# hw-art_v1.net
KiCad netlist of a schematic drawn in EAGLE
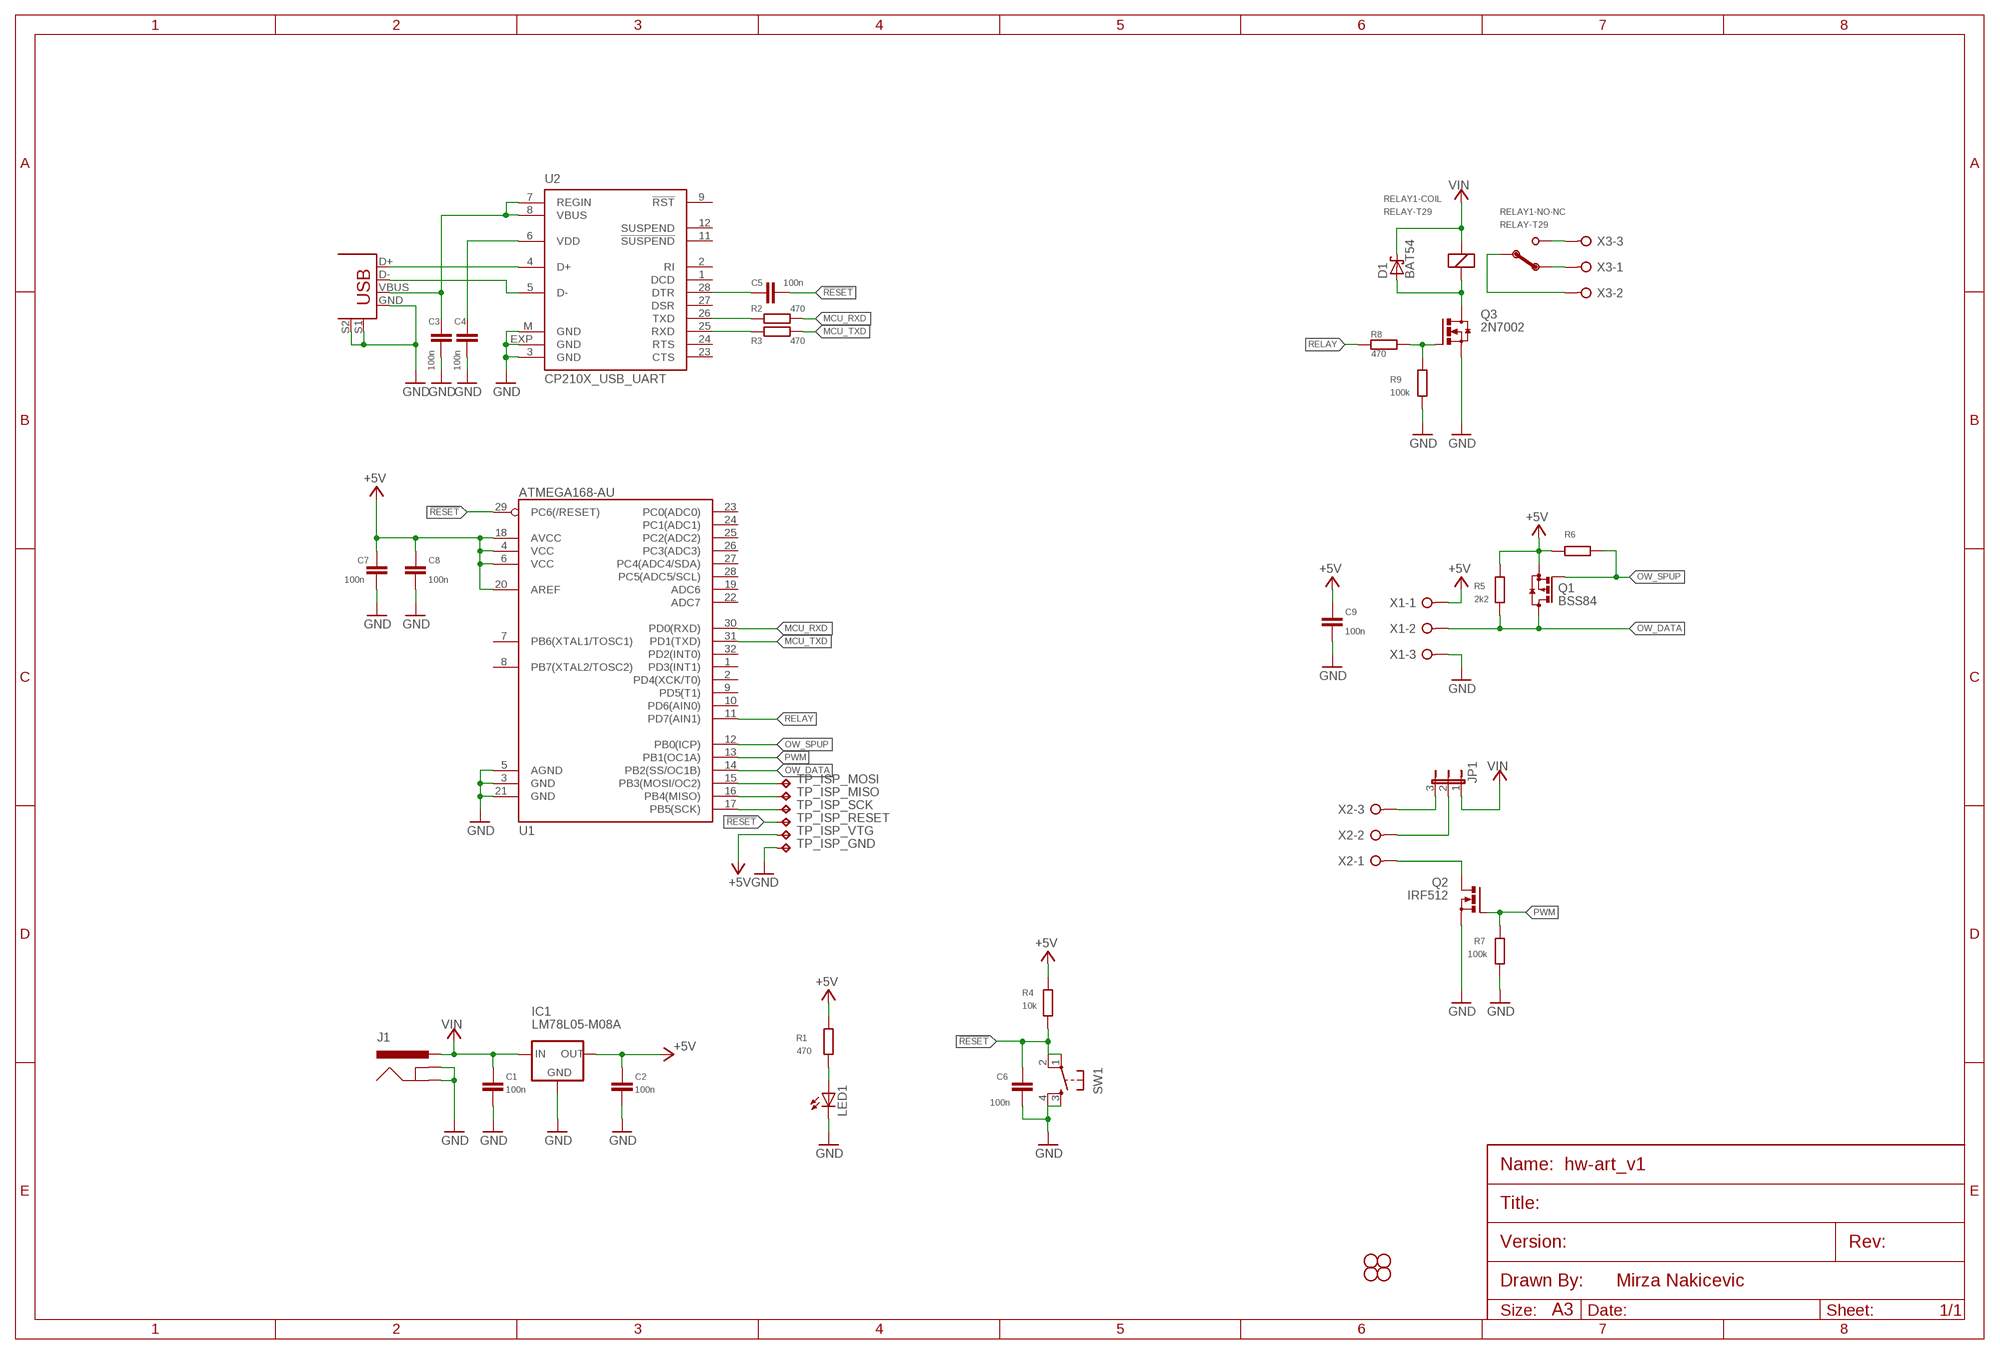
[diagram p0: schematic, sheet 1]

(export (version "E")
  (design (tool "Eeschema 10.0.6"))
  (components
    (comp (ref "C1")
      (value "100n")
      (footprint "eagle-import:C0603")
      (libsource (lib "eagle-import") (part "C-0603"))
    )
    (comp (ref "C2")
      (value "100n")
      (footprint "eagle-import:C0603")
      (libsource (lib "eagle-import") (part "C-0603"))
    )
    (comp (ref "C3")
      (value "100n")
      (footprint "eagle-import:C0603")
      (libsource (lib "eagle-import") (part "C-0603"))
    )
    (comp (ref "C4")
      (value "100n")
      (footprint "eagle-import:C0603")
      (libsource (lib "eagle-import") (part "C-0603"))
    )
    (comp (ref "C5")
      (value "100n")
      (footprint "eagle-import:C0603")
      (libsource (lib "eagle-import") (part "C-0603"))
    )
    (comp (ref "C6")
      (value "100n")
      (footprint "eagle-import:C0603")
      (libsource (lib "eagle-import") (part "C-0603"))
    )
    (comp (ref "C7")
      (value "100n")
      (footprint "eagle-import:C0603")
      (libsource (lib "eagle-import") (part "C-0603"))
    )
    (comp (ref "C8")
      (value "100n")
      (footprint "eagle-import:C0603")
      (libsource (lib "eagle-import") (part "C-0603"))
    )
    (comp (ref "C9")
      (value "100n")
      (footprint "eagle-import:C0603")
      (libsource (lib "eagle-import") (part "C-0603"))
    )
    (comp (ref "D1")
      (value "BAT54")
      (footprint "eagle-import:SOT23")
      (libsource (lib "eagle-import") (part "BAT54"))
    )
    (comp (ref "IC1")
      (value "LM78L05-M08A")
      (footprint "eagle-import:SO-08")
      (libsource (lib "eagle-import") (part "LM78L05-M08A"))
    )
    (comp (ref "J1")
      (value "DCJACK-05537")
      (footprint "eagle-import:4UCON-05537")
      (libsource (lib "eagle-import") (part "DCJACK-05537"))
    )
    (comp (ref "J2")
      (value "USB+SHIELD")
      (footprint "eagle-import:USB-B-PTH")
      (libsource (lib "eagle-import") (part "USB+SHIELD"))
    )
    (comp (ref "JP1")
      (value "JP2E")
      (footprint "eagle-import:JP2")
      (libsource (lib "eagle-import") (part "JP2E"))
    )
    (comp (ref "LED1")
      (value "LEDCHIP-LED0805")
      (footprint "eagle-import:CHIP-LED0805")
      (libsource (lib "eagle-import") (part "LEDCHIP-LED0805"))
    )
    (comp (ref "Q1")
      (value "BSS84")
      (footprint "eagle-import:SOT23")
      (libsource (lib "eagle-import") (part "BSS84"))
    )
    (comp (ref "Q2")
      (value "IRF512")
      (footprint "eagle-import:TO220BV")
      (libsource (lib "eagle-import") (part "IRF512"))
    )
    (comp (ref "Q3")
      (value "2N7002")
      (footprint "eagle-import:SOT-23")
      (libsource (lib "eagle-import") (part "2N7002"))
    )
    (comp (ref "R1")
      (value "470")
      (footprint "eagle-import:R0603")
      (libsource (lib "eagle-import") (part "R-0603"))
    )
    (comp (ref "R2")
      (value "470")
      (footprint "eagle-import:R0603")
      (libsource (lib "eagle-import") (part "R-0603"))
    )
    (comp (ref "R3")
      (value "470")
      (footprint "eagle-import:R0603")
      (libsource (lib "eagle-import") (part "R-0603"))
    )
    (comp (ref "R4")
      (value "10k")
      (footprint "eagle-import:R0603")
      (libsource (lib "eagle-import") (part "R-0603"))
    )
    (comp (ref "R5")
      (value "2k2")
      (footprint "eagle-import:R0603")
      (libsource (lib "eagle-import") (part "R-0603"))
    )
    (comp (ref "R6")
      (value "R-0603")
      (footprint "eagle-import:R0603")
      (libsource (lib "eagle-import") (part "R-0603"))
    )
    (comp (ref "R7")
      (value "100k")
      (footprint "eagle-import:R0603")
      (libsource (lib "eagle-import") (part "R-0603"))
    )
    (comp (ref "R8")
      (value "470")
      (footprint "eagle-import:R0603")
      (libsource (lib "eagle-import") (part "R-0603"))
    )
    (comp (ref "R9")
      (value "100k")
      (footprint "eagle-import:R0603")
      (libsource (lib "eagle-import") (part "R-0603"))
    )
    (comp (ref "RELAY1")
      (value "RELAY-T29")
      (footprint "eagle-import:FINDER_T29")
      (libsource (lib "eagle-import") (part "RELAY-T29"))
    )
    (comp (ref "SW1")
      (value "TAC_SWITCHPTH")
      (footprint "eagle-import:TACTILE-PTH")
      (libsource (lib "eagle-import") (part "TAC_SWITCHPTH"))
    )
    (comp (ref "TP_ISP_GND")
      (value "TPTP08R")
      (footprint "eagle-import:TP08R")
      (libsource (lib "eagle-import") (part "TPTP08R"))
    )
    (comp (ref "TP_ISP_MISO")
      (value "TPTP08R")
      (footprint "eagle-import:TP08R")
      (libsource (lib "eagle-import") (part "TPTP08R"))
    )
    (comp (ref "TP_ISP_MOSI")
      (value "TPTP08R")
      (footprint "eagle-import:TP08R")
      (libsource (lib "eagle-import") (part "TPTP08R"))
    )
    (comp (ref "TP_ISP_RESET")
      (value "TPTP08R")
      (footprint "eagle-import:TP08R")
      (libsource (lib "eagle-import") (part "TPTP08R"))
    )
    (comp (ref "TP_ISP_SCK")
      (value "TPTP08R")
      (footprint "eagle-import:TP08R")
      (libsource (lib "eagle-import") (part "TPTP08R"))
    )
    (comp (ref "TP_ISP_VTG")
      (value "TPTP08R")
      (footprint "eagle-import:TP08R")
      (libsource (lib "eagle-import") (part "TPTP08R"))
    )
    (comp (ref "U$1")
      (value "STAND-OFF")
      (footprint "eagle-import:STAND-OFF")
      (libsource (lib "eagle-import") (part "STAND-OFF"))
    )
    (comp (ref "U$2")
      (value "STAND-OFF")
      (footprint "eagle-import:STAND-OFF")
      (libsource (lib "eagle-import") (part "STAND-OFF"))
    )
    (comp (ref "U$3")
      (value "STAND-OFF")
      (footprint "eagle-import:STAND-OFF")
      (libsource (lib "eagle-import") (part "STAND-OFF"))
    )
    (comp (ref "U$4")
      (value "STAND-OFF")
      (footprint "eagle-import:STAND-OFF")
      (libsource (lib "eagle-import") (part "STAND-OFF"))
    )
    (comp (ref "U1")
      (value "ATMEGA168-AU")
      (footprint "eagle-import:TQFP32-08")
      (libsource (lib "eagle-import") (part "ATMEGA168-AU"))
    )
    (comp (ref "U2")
      (value "CP210X_USB_UART")
      (footprint "eagle-import:MLP28")
      (libsource (lib "eagle-import") (part "CP210X_USB_UART"))
    )
    (comp (ref "X1")
      (value "W237-03P")
      (footprint "eagle-import:W237-133")
      (libsource (lib "eagle-import") (part "W237-03P"))
    )
    (comp (ref "X2")
      (value "W237-03P")
      (footprint "eagle-import:W237-133")
      (libsource (lib "eagle-import") (part "W237-03P"))
    )
    (comp (ref "X3")
      (value "W237-03P")
      (footprint "eagle-import:W237-133")
      (libsource (lib "eagle-import") (part "W237-03P"))
    )
  )
  (nets
    (net (code "1") (name "+5V") (class "Default")
      (node (ref "C2") (pin "1") (pinfunction "1_1") (pintype "passive"))
      (node (ref "C7") (pin "1") (pinfunction "1_1") (pintype "passive"))
      (node (ref "C8") (pin "1") (pinfunction "1_1") (pintype "passive"))
      (node (ref "C9") (pin "1") (pinfunction "1_1") (pintype "passive"))
      (node (ref "IC1") (pin "1") (pinfunction "OUT_1") (pintype "output"))
      (node (ref "Q1") (pin "2") (pinfunction "S_2") (pintype "passive"))
      (node (ref "R1") (pin "2") (pinfunction "2_2") (pintype "passive"))
      (node (ref "R4") (pin "2") (pinfunction "2_2") (pintype "passive"))
      (node (ref "R5") (pin "2") (pinfunction "2_2") (pintype "passive"))
      (node (ref "R6") (pin "1") (pinfunction "1_1") (pintype "passive"))
      (node (ref "TP_ISP_VTG") (pin "TP") (pinfunction "TP_TP") (pintype "input"))
      (node (ref "U1") (pin "18") (pinfunction "AVCC_18") (pintype "bidirectional"))
      (node (ref "U1") (pin "20") (pinfunction "AREF_20") (pintype "bidirectional"))
      (node (ref "U1") (pin "4") (pinfunction "VCC_4") (pintype "bidirectional"))
      (node (ref "U1") (pin "6") (pinfunction "VCC_6") (pintype "bidirectional"))
      (node (ref "X1") (pin "1") (pinfunction "KL_1") (pintype "passive"))
    )
    (net (code "2") (name "/~{RESET}") (class "Default")
      (node (ref "C5") (pin "2") (pinfunction "2_2") (pintype "passive"))
      (node (ref "C6") (pin "2") (pinfunction "2_2") (pintype "passive"))
      (node (ref "R4") (pin "1") (pinfunction "1_1") (pintype "passive"))
      (node (ref "SW1") (pin "1") (pinfunction "1_1") (pintype "passive"))
      (node (ref "SW1") (pin "2") (pinfunction "2_2") (pintype "passive"))
      (node (ref "TP_ISP_RESET") (pin "TP") (pinfunction "TP_TP") (pintype "input"))
      (node (ref "U1") (pin "29") (pinfunction "PC6(/RESET)_29") (pintype "bidirectional"))
    )
    (net (code "3") (name "GND") (class "Default")
      (node (ref "C1") (pin "2") (pinfunction "2_2") (pintype "passive"))
      (node (ref "C2") (pin "2") (pinfunction "2_2") (pintype "passive"))
      (node (ref "C3") (pin "2") (pinfunction "2_2") (pintype "passive"))
      (node (ref "C4") (pin "2") (pinfunction "2_2") (pintype "passive"))
      (node (ref "C6") (pin "1") (pinfunction "1_1") (pintype "passive"))
      (node (ref "C7") (pin "2") (pinfunction "2_2") (pintype "passive"))
      (node (ref "C8") (pin "2") (pinfunction "2_2") (pintype "passive"))
      (node (ref "C9") (pin "2") (pinfunction "2_2") (pintype "passive"))
      (node (ref "IC1") (pin "2") (pinfunction "GND_2") (pintype "input"))
      (node (ref "IC1") (pin "3") (pinfunction "GND_3") (pintype "input"))
      (node (ref "IC1") (pin "6") (pinfunction "GND_6") (pintype "input"))
      (node (ref "IC1") (pin "7") (pinfunction "GND_7") (pintype "input"))
      (node (ref "J1") (pin "2") (pinfunction "GND_2") (pintype "bidirectional"))
      (node (ref "J1") (pin "3") (pinfunction "GNDBREAK_3") (pintype "bidirectional"))
      (node (ref "J2") (pin "GND") (pinfunction "GND_GND") (pintype "bidirectional"))
      (node (ref "J2") (pin "S1") (pinfunction "P$1_S1") (pintype "bidirectional"))
      (node (ref "J2") (pin "S2") (pinfunction "P$2_S2") (pintype "bidirectional"))
      (node (ref "LED1") (pin "C") (pinfunction "C_C") (pintype "passive"))
      (node (ref "Q2") (pin "S") (pinfunction "S_S") (pintype "passive"))
      (node (ref "Q3") (pin "2") (pinfunction "S_2") (pintype "passive"))
      (node (ref "R7") (pin "2") (pinfunction "2_2") (pintype "passive"))
      (node (ref "R9") (pin "1") (pinfunction "1_1") (pintype "passive"))
      (node (ref "SW1") (pin "3") (pinfunction "3_3") (pintype "passive"))
      (node (ref "SW1") (pin "4") (pinfunction "4_4") (pintype "passive"))
      (node (ref "TP_ISP_GND") (pin "TP") (pinfunction "TP_TP") (pintype "input"))
      (node (ref "U1") (pin "21") (pinfunction "GND_21") (pintype "bidirectional"))
      (node (ref "U1") (pin "3") (pinfunction "GND_3") (pintype "bidirectional"))
      (node (ref "U1") (pin "5") (pinfunction "AGND_5") (pintype "bidirectional"))
      (node (ref "U2") (pin "3") (pinfunction "GND_3") (pintype "power_in"))
      (node (ref "U2") (pin "EXP") (pinfunction "GND_EXP") (pintype "power_in"))
      (node (ref "U2") (pin "M") (pinfunction "GND_M") (pintype "power_in"))
      (node (ref "X1") (pin "3") (pinfunction "KL_3") (pintype "passive"))
    )
    (net (code "4") (name "MCU_RXD") (class "Default")
      (node (ref "R2") (pin "2") (pinfunction "2_2") (pintype "passive"))
      (node (ref "U1") (pin "30") (pinfunction "PD0(RXD)_30") (pintype "bidirectional"))
    )
    (net (code "5") (name "MCU_TXD") (class "Default")
      (node (ref "R3") (pin "2") (pinfunction "2_2") (pintype "passive"))
      (node (ref "U1") (pin "31") (pinfunction "PD1(TXD)_31") (pintype "bidirectional"))
    )
    (net (code "6") (name "Net-(D1-A)") (class "Default")
      (node (ref "D1") (pin "1") (pinfunction "A_1") (pintype "passive"))
      (node (ref "Q3") (pin "3") (pinfunction "D_3") (pintype "passive"))
      (node (ref "RELAY1") (pin "-") (pinfunction "P$2_-") (pintype "bidirectional"))
    )
    (net (code "7") (name "Net-(LED1-PadA)") (class "Default")
      (node (ref "LED1") (pin "A") (pinfunction "A_A") (pintype "passive"))
      (node (ref "R1") (pin "1") (pinfunction "1_1") (pintype "passive"))
    )
    (net (code "8") (name "Net-(Q3-G)") (class "Default")
      (node (ref "Q3") (pin "1") (pinfunction "G_1") (pintype "passive"))
      (node (ref "R8") (pin "1") (pinfunction "1_1") (pintype "passive"))
      (node (ref "R9") (pin "2") (pinfunction "2_2") (pintype "passive"))
    )
    (net (code "9") (name "Net-(U1-PB3(MOSI{slash}OC2))") (class "Default")
      (node (ref "TP_ISP_MOSI") (pin "TP") (pinfunction "TP_TP") (pintype "input"))
      (node (ref "U1") (pin "15") (pinfunction "PB3(MOSI/OC2)_15") (pintype "bidirectional"))
    )
    (net (code "10") (name "Net-(U1-PB4(MISO))") (class "Default")
      (node (ref "TP_ISP_MISO") (pin "TP") (pinfunction "TP_TP") (pintype "input"))
      (node (ref "U1") (pin "16") (pinfunction "PB4(MISO)_16") (pintype "bidirectional"))
    )
    (net (code "11") (name "Net-(U1-PB5(SCK))") (class "Default")
      (node (ref "TP_ISP_SCK") (pin "TP") (pinfunction "TP_TP") (pintype "input"))
      (node (ref "U1") (pin "17") (pinfunction "PB5(SCK)_17") (pintype "bidirectional"))
    )
    (net (code "12") (name "Net-(U2-D+)") (class "Default")
      (node (ref "J2") (pin "D+") (pinfunction "D+_D+") (pintype "bidirectional"))
      (node (ref "U2") (pin "4") (pinfunction "D+_4") (pintype "bidirectional"))
    )
    (net (code "13") (name "Net-(U2-D-)") (class "Default")
      (node (ref "J2") (pin "D-") (pinfunction "D-_D-") (pintype "bidirectional"))
      (node (ref "U2") (pin "5") (pinfunction "D-_5") (pintype "bidirectional"))
    )
    (net (code "14") (name "Net-(U2-DTR)") (class "Default")
      (node (ref "C5") (pin "1") (pinfunction "1_1") (pintype "passive"))
      (node (ref "U2") (pin "28") (pinfunction "DTR_28") (pintype "output"))
    )
    (net (code "15") (name "Net-(U2-REGIN)") (class "Default")
      (node (ref "C3") (pin "1") (pinfunction "1_1") (pintype "passive"))
      (node (ref "J2") (pin "VBUS") (pinfunction "VBUS_VBUS") (pintype "bidirectional"))
      (node (ref "U2") (pin "7") (pinfunction "REGIN_7") (pintype "passive"))
      (node (ref "U2") (pin "8") (pinfunction "VBUS_8") (pintype "input"))
    )
    (net (code "16") (name "Net-(U2-RXD)") (class "Default")
      (node (ref "R3") (pin "1") (pinfunction "1_1") (pintype "passive"))
      (node (ref "U2") (pin "25") (pinfunction "RXD_25") (pintype "input"))
    )
    (net (code "17") (name "Net-(U2-TXD)") (class "Default")
      (node (ref "R2") (pin "1") (pinfunction "1_1") (pintype "passive"))
      (node (ref "U2") (pin "26") (pinfunction "TXD_26") (pintype "output"))
    )
    (net (code "18") (name "Net-(U2-VDD)") (class "Default")
      (node (ref "C4") (pin "1") (pinfunction "1_1") (pintype "passive"))
      (node (ref "U2") (pin "6") (pinfunction "VDD_6") (pintype "power_in"))
    )
    (net (code "19") (name "Net-(X2A-KL)") (class "Default")
      (node (ref "Q2") (pin "D") (pinfunction "D_D") (pintype "passive"))
      (node (ref "X2") (pin "1") (pinfunction "KL_1") (pintype "passive"))
    )
    (net (code "20") (name "Net-(X2B-KL)") (class "Default")
      (node (ref "JP1") (pin "2") (pinfunction "2_2") (pintype "passive"))
      (node (ref "X2") (pin "2") (pinfunction "KL_2") (pintype "passive"))
    )
    (net (code "21") (name "Net-(X2C-KL)") (class "Default")
      (node (ref "JP1") (pin "3") (pinfunction "3_3") (pintype "passive"))
      (node (ref "X2") (pin "3") (pinfunction "KL_3") (pintype "passive"))
    )
    (net (code "22") (name "Net-(X3A-KL)") (class "Default")
      (node (ref "RELAY1") (pin "NC") (pinfunction "NC_NC") (pintype "bidirectional"))
      (node (ref "X3") (pin "1") (pinfunction "KL_1") (pintype "passive"))
    )
    (net (code "23") (name "Net-(X3B-KL)") (class "Default")
      (node (ref "RELAY1") (pin "COM") (pinfunction "COM_COM") (pintype "bidirectional"))
      (node (ref "X3") (pin "2") (pinfunction "KL_2") (pintype "passive"))
    )
    (net (code "24") (name "Net-(X3C-KL)") (class "Default")
      (node (ref "RELAY1") (pin "NO") (pinfunction "NO_NO") (pintype "bidirectional"))
      (node (ref "X3") (pin "3") (pinfunction "KL_3") (pintype "passive"))
    )
    (net (code "25") (name "OW_DATA") (class "Default")
      (node (ref "Q1") (pin "3") (pinfunction "D_3") (pintype "passive"))
      (node (ref "R5") (pin "1") (pinfunction "1_1") (pintype "passive"))
      (node (ref "U1") (pin "14") (pinfunction "PB2(SS/OC1B)_14") (pintype "bidirectional"))
      (node (ref "X1") (pin "2") (pinfunction "KL_2") (pintype "passive"))
    )
    (net (code "26") (name "OW_SPUP") (class "Default")
      (node (ref "Q1") (pin "1") (pinfunction "G_1") (pintype "passive"))
      (node (ref "R6") (pin "2") (pinfunction "2_2") (pintype "passive"))
      (node (ref "U1") (pin "12") (pinfunction "PB0(ICP)_12") (pintype "bidirectional"))
    )
    (net (code "27") (name "PWM") (class "Default")
      (node (ref "Q2") (pin "G") (pinfunction "G_G") (pintype "passive"))
      (node (ref "R7") (pin "1") (pinfunction "1_1") (pintype "passive"))
      (node (ref "U1") (pin "13") (pinfunction "PB1(OC1A)_13") (pintype "bidirectional"))
    )
    (net (code "28") (name "RELAY") (class "Default")
      (node (ref "R8") (pin "2") (pinfunction "2_2") (pintype "passive"))
      (node (ref "U1") (pin "11") (pinfunction "PD7(AIN1)_11") (pintype "bidirectional"))
    )
    (net (code "29") (name "VIN") (class "Default")
      (node (ref "C1") (pin "1") (pinfunction "1_1") (pintype "passive"))
      (node (ref "D1") (pin "3") (pinfunction "C_3") (pintype "passive"))
      (node (ref "IC1") (pin "8") (pinfunction "IN_8") (pintype "input"))
      (node (ref "J1") (pin "1") (pinfunction "PWR_1") (pintype "bidirectional"))
      (node (ref "JP1") (pin "1") (pinfunction "1_1") (pintype "passive"))
      (node (ref "RELAY1") (pin "+") (pinfunction "P$1_+") (pintype "bidirectional"))
    )
    (net (code "30") (name "unconnected-(U1-ADC6-Pad19)") (class "Default")
      (node (ref "U1") (pin "19") (pinfunction "ADC6_19") (pintype "bidirectional"))
    )
    (net (code "31") (name "unconnected-(U1-ADC7-Pad22)") (class "Default")
      (node (ref "U1") (pin "22") (pinfunction "ADC7_22") (pintype "bidirectional"))
    )
    (net (code "32") (name "unconnected-(U1-PB6(XTAL1{slash}TOSC1)-Pad7)") (class "Default")
      (node (ref "U1") (pin "7") (pinfunction "PB6(XTAL1/TOSC1)_7") (pintype "bidirectional"))
    )
    (net (code "33") (name "unconnected-(U1-PB7(XTAL2{slash}TOSC2)-Pad8)") (class "Default")
      (node (ref "U1") (pin "8") (pinfunction "PB7(XTAL2/TOSC2)_8") (pintype "bidirectional"))
    )
    (net (code "34") (name "unconnected-(U1-PC0(ADC0)-Pad23)") (class "Default")
      (node (ref "U1") (pin "23") (pinfunction "PC0(ADC0)_23") (pintype "bidirectional"))
    )
    (net (code "35") (name "unconnected-(U1-PC1(ADC1)-Pad24)") (class "Default")
      (node (ref "U1") (pin "24") (pinfunction "PC1(ADC1)_24") (pintype "bidirectional"))
    )
    (net (code "36") (name "unconnected-(U1-PC2(ADC2)-Pad25)") (class "Default")
      (node (ref "U1") (pin "25") (pinfunction "PC2(ADC2)_25") (pintype "bidirectional"))
    )
    (net (code "37") (name "unconnected-(U1-PC3(ADC3)-Pad26)") (class "Default")
      (node (ref "U1") (pin "26") (pinfunction "PC3(ADC3)_26") (pintype "bidirectional"))
    )
    (net (code "38") (name "unconnected-(U1-PC4(ADC4{slash}SDA)-Pad27)") (class "Default")
      (node (ref "U1") (pin "27") (pinfunction "PC4(ADC4/SDA)_27") (pintype "bidirectional"))
    )
    (net (code "39") (name "unconnected-(U1-PC5(ADC5{slash}SCL)-Pad28)") (class "Default")
      (node (ref "U1") (pin "28") (pinfunction "PC5(ADC5/SCL)_28") (pintype "bidirectional"))
    )
    (net (code "40") (name "unconnected-(U1-PD2(INT0)-Pad32)") (class "Default")
      (node (ref "U1") (pin "32") (pinfunction "PD2(INT0)_32") (pintype "bidirectional"))
    )
    (net (code "41") (name "unconnected-(U1-PD3(INT1)-Pad1)") (class "Default")
      (node (ref "U1") (pin "1") (pinfunction "PD3(INT1)_1") (pintype "bidirectional"))
    )
    (net (code "42") (name "unconnected-(U1-PD4(XCK{slash}T0)-Pad2)") (class "Default")
      (node (ref "U1") (pin "2") (pinfunction "PD4(XCK/T0)_2") (pintype "bidirectional"))
    )
    (net (code "43") (name "unconnected-(U1-PD5(T1)-Pad9)") (class "Default")
      (node (ref "U1") (pin "9") (pinfunction "PD5(T1)_9") (pintype "bidirectional"))
    )
    (net (code "44") (name "unconnected-(U1-PD6(AIN0)-Pad10)") (class "Default")
      (node (ref "U1") (pin "10") (pinfunction "PD6(AIN0)_10") (pintype "bidirectional"))
    )
    (net (code "45") (name "unconnected-(U2-CTS-Pad23)") (class "Default")
      (node (ref "U2") (pin "23") (pinfunction "CTS_23") (pintype "input"))
    )
    (net (code "46") (name "unconnected-(U2-DCD-Pad1)") (class "Default")
      (node (ref "U2") (pin "1") (pinfunction "DCD_1") (pintype "input"))
    )
    (net (code "47") (name "unconnected-(U2-DSR-Pad27)") (class "Default")
      (node (ref "U2") (pin "27") (pinfunction "DSR_27") (pintype "input"))
    )
    (net (code "48") (name "unconnected-(U2-RI-Pad2)") (class "Default")
      (node (ref "U2") (pin "2") (pinfunction "RI_2") (pintype "input"))
    )
    (net (code "49") (name "unconnected-(U2-RTS-Pad24)") (class "Default")
      (node (ref "U2") (pin "24") (pinfunction "RTS_24") (pintype "output"))
    )
    (net (code "50") (name "unconnected-(U2-SUSPEND-Pad12)") (class "Default")
      (node (ref "U2") (pin "12") (pinfunction "SUSPEND_12") (pintype "output"))
    )
    (net (code "51") (name "unconnected-(U2-~{RST}-Pad9)") (class "Default")
      (node (ref "U2") (pin "9") (pinfunction "~{RST}_9") (pintype "bidirectional"))
    )
    (net (code "52") (name "unconnected-(U2-~{SUSPEND}-Pad11)") (class "Default")
      (node (ref "U2") (pin "11") (pinfunction "~{SUSPEND}_11") (pintype "output"))
    )
  )
)
